# Ninja-towns_modular.net
KiCad netlist of a schematic drawn in EAGLE
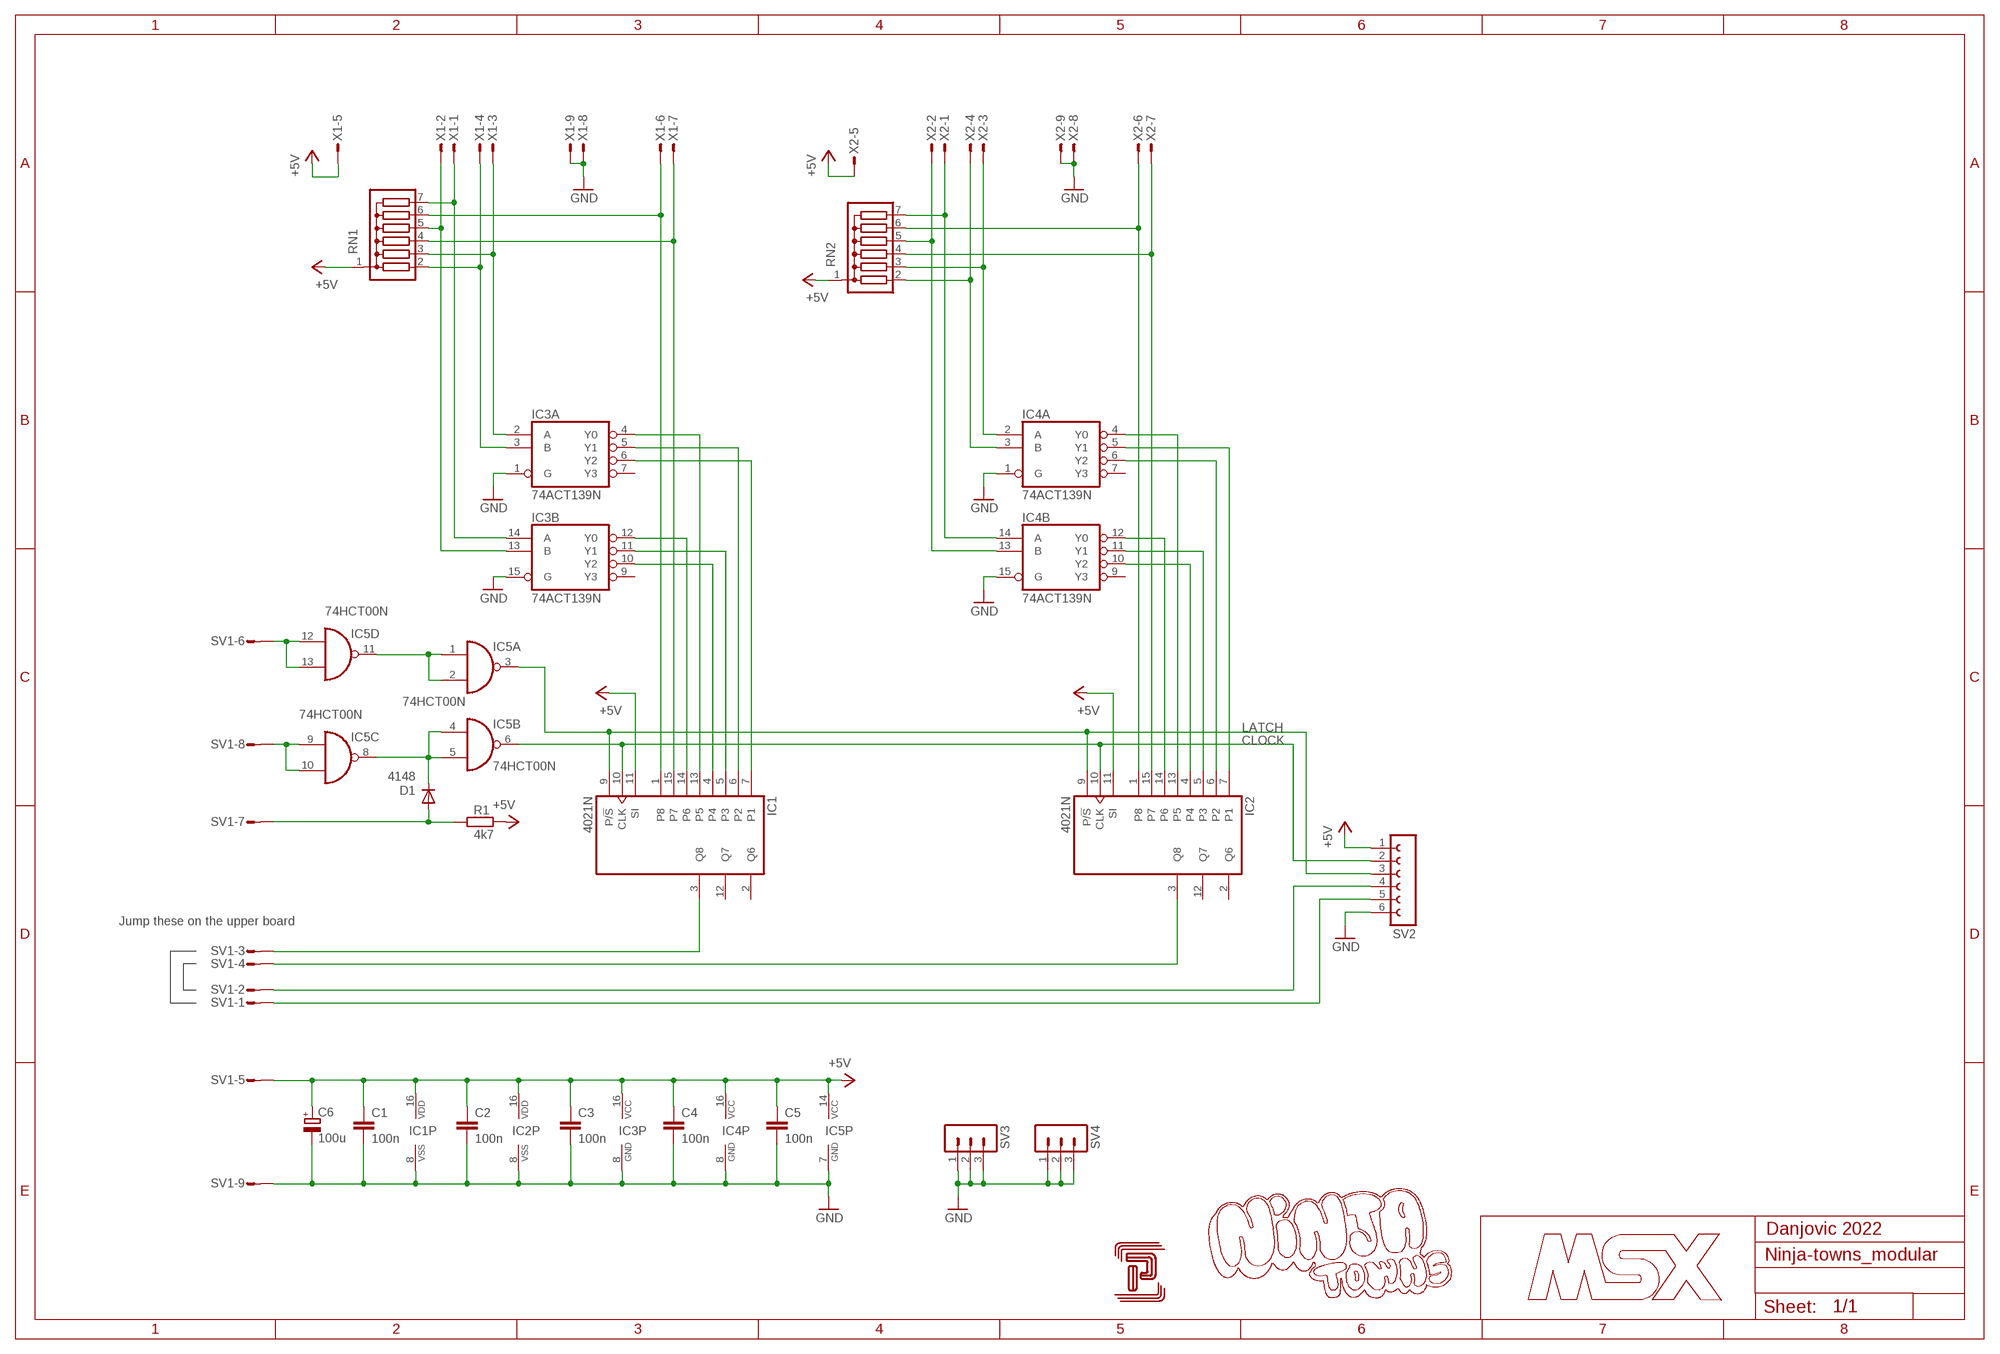
[diagram p0: schematic, sheet 1]

(export (version "E")
  (design (tool "Eeschema 10.0.6"))
  (components
    (comp (ref "C1")
      (value "100n")
      (footprint "eagle-import:C050-024X044")
      (libsource (lib "eagle-import") (part "C-EU050-024X044"))
    )
    (comp (ref "C2")
      (value "100n")
      (footprint "eagle-import:C050-024X044")
      (libsource (lib "eagle-import") (part "C-EU050-024X044"))
    )
    (comp (ref "C3")
      (value "100n")
      (footprint "eagle-import:C050-024X044")
      (libsource (lib "eagle-import") (part "C-EU050-024X044"))
    )
    (comp (ref "C4")
      (value "100n")
      (footprint "eagle-import:C050-024X044")
      (libsource (lib "eagle-import") (part "C-EU050-024X044"))
    )
    (comp (ref "C5")
      (value "100n")
      (footprint "eagle-import:C050-024X044")
      (libsource (lib "eagle-import") (part "C-EU050-024X044"))
    )
    (comp (ref "C6")
      (value "100u")
      (footprint "eagle-import:E2,5-6")
      (libsource (lib "eagle-import") (part "CPOL-EUE2.5-6"))
    )
    (comp (ref "D1")
      (value "4148")
      (footprint "eagle-import:D-5")
      (libsource (lib "eagle-import") (part "DIODE-D-5"))
    )
    (comp (ref "IC1")
      (value "4021N")
      (footprint "eagle-import:DIL16")
      (libsource (lib "eagle-import") (part "4021N"))
    )
    (comp (ref "IC2")
      (value "4021N")
      (footprint "eagle-import:DIL16")
      (libsource (lib "eagle-import") (part "4021N"))
    )
    (comp (ref "IC3")
      (value "74ACT139N")
      (footprint "eagle-import:DIL16")
      (libsource (lib "eagle-import") (part "74139NACT"))
    )
    (comp (ref "IC4")
      (value "74ACT139N")
      (footprint "eagle-import:DIL16")
      (libsource (lib "eagle-import") (part "74139NACT"))
    )
    (comp (ref "IC5")
      (value "74HCT00N")
      (footprint "eagle-import:DIL14")
      (libsource (lib "eagle-import") (part "7400NHCT"))
    )
    (comp (ref "R1")
      (value "4k7")
      (footprint "eagle-import:0204_7L")
      (libsource (lib "eagle-import") (part "R-EU_0204/7L"))
    )
    (comp (ref "RN1")
      (value "G06R")
      (footprint "eagle-import:SIL7")
      (libsource (lib "eagle-import") (part "G06R"))
    )
    (comp (ref "RN2")
      (value "G06R")
      (footprint "eagle-import:SIL7")
      (libsource (lib "eagle-import") (part "G06R"))
    )
    (comp (ref "SV1")
      (value "S09P")
      (footprint "eagle-import:S09P")
      (libsource (lib "eagle-import") (part "S09P"))
    )
    (comp (ref "SV2")
      (value "FE06-1")
      (footprint "eagle-import:FE06")
      (libsource (lib "eagle-import") (part "FE06-1"))
    )
    (comp (ref "SV3")
      (value "MA03-1")
      (footprint "eagle-import:MA03-1")
      (libsource (lib "eagle-import") (part "MA03-1"))
    )
    (comp (ref "SV4")
      (value "MA03-1")
      (footprint "eagle-import:MA03-1")
      (libsource (lib "eagle-import") (part "MA03-1"))
    )
    (comp (ref "U$1")
      (value "PB-203_TOP")
      (footprint "eagle-import:PB203-TOP")
      (libsource (lib "eagle-import") (part "PB-203_TOP"))
    )
    (comp (ref "X1")
      (value "M09-182S")
      (footprint "eagle-import:182-009-MALE")
      (libsource (lib "eagle-import") (part "M09?S-182"))
    )
    (comp (ref "X2")
      (value "M09-182S")
      (footprint "eagle-import:182-009-MALE")
      (libsource (lib "eagle-import") (part "M09?S-182"))
    )
  )
  (nets
    (net (code "1") (name "+5V") (class "Default")
      (node (ref "C1") (pin "1") (pinfunction "1_1") (pintype "passive"))
      (node (ref "C2") (pin "1") (pinfunction "1_1") (pintype "passive"))
      (node (ref "C3") (pin "1") (pinfunction "1_1") (pintype "passive"))
      (node (ref "C4") (pin "1") (pinfunction "1_1") (pintype "passive"))
      (node (ref "C5") (pin "1") (pinfunction "1_1") (pintype "passive"))
      (node (ref "C6") (pin "+") (pinfunction "+_+") (pintype "passive"))
      (node (ref "IC1") (pin "11") (pinfunction "SI_11") (pintype "input"))
      (node (ref "IC1") (pin "16") (pinfunction "VDD_16") (pintype "power_in"))
      (node (ref "IC2") (pin "11") (pinfunction "SI_11") (pintype "input"))
      (node (ref "IC2") (pin "16") (pinfunction "VDD_16") (pintype "power_in"))
      (node (ref "IC3") (pin "16") (pinfunction "VCC_16") (pintype "power_in"))
      (node (ref "IC4") (pin "16") (pinfunction "VCC_16") (pintype "power_in"))
      (node (ref "IC5") (pin "14") (pinfunction "VCC_14") (pintype "power_in"))
      (node (ref "R1") (pin "1") (pinfunction "1_1") (pintype "passive"))
      (node (ref "RN1") (pin "1") (pinfunction "1_1") (pintype "passive"))
      (node (ref "RN2") (pin "1") (pinfunction "1_1") (pintype "passive"))
      (node (ref "SV1") (pin "5") (pinfunction "S_5") (pintype "passive"))
      (node (ref "SV2") (pin "1") (pinfunction "1_1") (pintype "passive"))
      (node (ref "X1") (pin "5") (pinfunction "M_5") (pintype "passive"))
      (node (ref "X2") (pin "5") (pinfunction "M_5") (pintype "passive"))
    )
    (net (code "2") (name "/CLOCK") (class "Default")
      (node (ref "IC1") (pin "10") (pinfunction "CLK_10") (pintype "input"))
      (node (ref "IC2") (pin "10") (pinfunction "CLK_10") (pintype "input"))
      (node (ref "IC5") (pin "6") (pinfunction "O_6") (pintype "output"))
      (node (ref "SV2") (pin "2") (pinfunction "2_2") (pintype "passive"))
    )
    (net (code "3") (name "/LATCH") (class "Default")
      (node (ref "IC1") (pin "9") (pinfunction "P/~{S}_9") (pintype "input"))
      (node (ref "IC2") (pin "9") (pinfunction "P/~{S}_9") (pintype "input"))
      (node (ref "IC5") (pin "3") (pinfunction "O_3") (pintype "output"))
      (node (ref "SV2") (pin "3") (pinfunction "3_3") (pintype "passive"))
    )
    (net (code "4") (name "GND") (class "Default")
      (node (ref "C1") (pin "2") (pinfunction "2_2") (pintype "passive"))
      (node (ref "C2") (pin "2") (pinfunction "2_2") (pintype "passive"))
      (node (ref "C3") (pin "2") (pinfunction "2_2") (pintype "passive"))
      (node (ref "C4") (pin "2") (pinfunction "2_2") (pintype "passive"))
      (node (ref "C5") (pin "2") (pinfunction "2_2") (pintype "passive"))
      (node (ref "C6") (pin "-") (pinfunction "-_-") (pintype "passive"))
      (node (ref "IC1") (pin "8") (pinfunction "VSS_8") (pintype "power_in"))
      (node (ref "IC2") (pin "8") (pinfunction "VSS_8") (pintype "power_in"))
      (node (ref "IC3") (pin "1") (pinfunction "G_1") (pintype "input"))
      (node (ref "IC3") (pin "15") (pinfunction "G_15") (pintype "input"))
      (node (ref "IC3") (pin "8") (pinfunction "GND_8") (pintype "power_in"))
      (node (ref "IC4") (pin "1") (pinfunction "G_1") (pintype "input"))
      (node (ref "IC4") (pin "15") (pinfunction "G_15") (pintype "input"))
      (node (ref "IC4") (pin "8") (pinfunction "GND_8") (pintype "power_in"))
      (node (ref "IC5") (pin "7") (pinfunction "GND_7") (pintype "power_in"))
      (node (ref "SV1") (pin "9") (pinfunction "S_9") (pintype "passive"))
      (node (ref "SV2") (pin "6") (pinfunction "6_6") (pintype "passive"))
      (node (ref "SV3") (pin "1") (pinfunction "1_1") (pintype "passive"))
      (node (ref "SV3") (pin "2") (pinfunction "2_2") (pintype "passive"))
      (node (ref "SV3") (pin "3") (pinfunction "3_3") (pintype "passive"))
      (node (ref "SV4") (pin "1") (pinfunction "1_1") (pintype "passive"))
      (node (ref "SV4") (pin "2") (pinfunction "2_2") (pintype "passive"))
      (node (ref "SV4") (pin "3") (pinfunction "3_3") (pintype "passive"))
      (node (ref "X1") (pin "8") (pinfunction "M_8") (pintype "passive"))
      (node (ref "X1") (pin "9") (pinfunction "M_9") (pintype "passive"))
      (node (ref "X2") (pin "8") (pinfunction "M_8") (pintype "passive"))
      (node (ref "X2") (pin "9") (pinfunction "M_9") (pintype "passive"))
    )
    (net (code "5") (name "Net-(IC1A-P1)") (class "Default")
      (node (ref "IC1") (pin "7") (pinfunction "P1_7") (pintype "input"))
      (node (ref "IC3") (pin "6") (pinfunction "Y2_6") (pintype "output"))
    )
    (net (code "6") (name "Net-(IC1A-P2)") (class "Default")
      (node (ref "IC1") (pin "6") (pinfunction "P2_6") (pintype "input"))
      (node (ref "IC3") (pin "5") (pinfunction "Y1_5") (pintype "output"))
    )
    (net (code "7") (name "Net-(IC1A-P3)") (class "Default")
      (node (ref "IC1") (pin "5") (pinfunction "P3_5") (pintype "input"))
      (node (ref "IC3") (pin "11") (pinfunction "Y1_11") (pintype "output"))
    )
    (net (code "8") (name "Net-(IC1A-P4)") (class "Default")
      (node (ref "IC1") (pin "4") (pinfunction "P4_4") (pintype "input"))
      (node (ref "IC3") (pin "10") (pinfunction "Y2_10") (pintype "output"))
    )
    (net (code "9") (name "Net-(IC1A-P5)") (class "Default")
      (node (ref "IC1") (pin "13") (pinfunction "P5_13") (pintype "input"))
      (node (ref "IC3") (pin "4") (pinfunction "Y0_4") (pintype "output"))
    )
    (net (code "10") (name "Net-(IC1A-P6)") (class "Default")
      (node (ref "IC1") (pin "14") (pinfunction "P6_14") (pintype "input"))
      (node (ref "IC3") (pin "12") (pinfunction "Y0_12") (pintype "output"))
    )
    (net (code "11") (name "Net-(IC1A-P7)") (class "Default")
      (node (ref "IC1") (pin "15") (pinfunction "P7_15") (pintype "input"))
      (node (ref "RN1") (pin "4") (pinfunction "4_4") (pintype "passive"))
      (node (ref "X1") (pin "7") (pinfunction "M_7") (pintype "passive"))
    )
    (net (code "12") (name "Net-(IC1A-P8)") (class "Default")
      (node (ref "IC1") (pin "1") (pinfunction "P8_1") (pintype "input"))
      (node (ref "RN1") (pin "6") (pinfunction "6_6") (pintype "passive"))
      (node (ref "X1") (pin "6") (pinfunction "M_6") (pintype "passive"))
    )
    (net (code "13") (name "Net-(IC1A-Q8)") (class "Default")
      (node (ref "IC1") (pin "3") (pinfunction "Q8_3") (pintype "output"))
      (node (ref "SV1") (pin "3") (pinfunction "S_3") (pintype "passive"))
    )
    (net (code "14") (name "Net-(IC2A-P1)") (class "Default")
      (node (ref "IC2") (pin "7") (pinfunction "P1_7") (pintype "input"))
      (node (ref "IC4") (pin "5") (pinfunction "Y1_5") (pintype "output"))
    )
    (net (code "15") (name "Net-(IC2A-P2)") (class "Default")
      (node (ref "IC2") (pin "6") (pinfunction "P2_6") (pintype "input"))
      (node (ref "IC4") (pin "6") (pinfunction "Y2_6") (pintype "output"))
    )
    (net (code "16") (name "Net-(IC2A-P3)") (class "Default")
      (node (ref "IC2") (pin "5") (pinfunction "P3_5") (pintype "input"))
      (node (ref "IC4") (pin "11") (pinfunction "Y1_11") (pintype "output"))
    )
    (net (code "17") (name "Net-(IC2A-P4)") (class "Default")
      (node (ref "IC2") (pin "4") (pinfunction "P4_4") (pintype "input"))
      (node (ref "IC4") (pin "10") (pinfunction "Y2_10") (pintype "output"))
    )
    (net (code "18") (name "Net-(IC2A-P5)") (class "Default")
      (node (ref "IC2") (pin "13") (pinfunction "P5_13") (pintype "input"))
      (node (ref "IC4") (pin "4") (pinfunction "Y0_4") (pintype "output"))
    )
    (net (code "19") (name "Net-(IC2A-P6)") (class "Default")
      (node (ref "IC2") (pin "14") (pinfunction "P6_14") (pintype "input"))
      (node (ref "IC4") (pin "12") (pinfunction "Y0_12") (pintype "output"))
    )
    (net (code "20") (name "Net-(IC2A-P7)") (class "Default")
      (node (ref "IC2") (pin "15") (pinfunction "P7_15") (pintype "input"))
      (node (ref "RN2") (pin "4") (pinfunction "4_4") (pintype "passive"))
      (node (ref "X2") (pin "7") (pinfunction "M_7") (pintype "passive"))
    )
    (net (code "21") (name "Net-(IC2A-P8)") (class "Default")
      (node (ref "IC2") (pin "1") (pinfunction "P8_1") (pintype "input"))
      (node (ref "RN2") (pin "6") (pinfunction "6_6") (pintype "passive"))
      (node (ref "X2") (pin "6") (pinfunction "M_6") (pintype "passive"))
    )
    (net (code "22") (name "Net-(IC2A-Q8)") (class "Default")
      (node (ref "IC2") (pin "3") (pinfunction "Q8_3") (pintype "output"))
      (node (ref "SV1") (pin "4") (pinfunction "S_4") (pintype "passive"))
    )
    (net (code "23") (name "Net-(IC3A-A)") (class "Default")
      (node (ref "IC3") (pin "2") (pinfunction "A_2") (pintype "input"))
      (node (ref "RN1") (pin "3") (pinfunction "3_3") (pintype "passive"))
      (node (ref "X1") (pin "3") (pinfunction "M_3") (pintype "passive"))
    )
    (net (code "24") (name "Net-(IC3A-B)") (class "Default")
      (node (ref "IC3") (pin "3") (pinfunction "B_3") (pintype "input"))
      (node (ref "RN1") (pin "2") (pinfunction "2_2") (pintype "passive"))
      (node (ref "X1") (pin "4") (pinfunction "M_4") (pintype "passive"))
    )
    (net (code "25") (name "Net-(IC3B-A)") (class "Default")
      (node (ref "IC3") (pin "14") (pinfunction "A_14") (pintype "input"))
      (node (ref "RN1") (pin "7") (pinfunction "7_7") (pintype "passive"))
      (node (ref "X1") (pin "1") (pinfunction "M_1") (pintype "passive"))
    )
    (net (code "26") (name "Net-(IC3B-B)") (class "Default")
      (node (ref "IC3") (pin "13") (pinfunction "B_13") (pintype "input"))
      (node (ref "RN1") (pin "5") (pinfunction "5_5") (pintype "passive"))
      (node (ref "X1") (pin "2") (pinfunction "M_2") (pintype "passive"))
    )
    (net (code "27") (name "Net-(IC4A-A)") (class "Default")
      (node (ref "IC4") (pin "2") (pinfunction "A_2") (pintype "input"))
      (node (ref "RN2") (pin "3") (pinfunction "3_3") (pintype "passive"))
      (node (ref "X2") (pin "3") (pinfunction "M_3") (pintype "passive"))
    )
    (net (code "28") (name "Net-(IC4A-B)") (class "Default")
      (node (ref "IC4") (pin "3") (pinfunction "B_3") (pintype "input"))
      (node (ref "RN2") (pin "2") (pinfunction "2_2") (pintype "passive"))
      (node (ref "X2") (pin "4") (pinfunction "M_4") (pintype "passive"))
    )
    (net (code "29") (name "Net-(IC4B-A)") (class "Default")
      (node (ref "IC4") (pin "14") (pinfunction "A_14") (pintype "input"))
      (node (ref "RN2") (pin "7") (pinfunction "7_7") (pintype "passive"))
      (node (ref "X2") (pin "1") (pinfunction "M_1") (pintype "passive"))
    )
    (net (code "30") (name "Net-(IC4B-B)") (class "Default")
      (node (ref "IC4") (pin "13") (pinfunction "B_13") (pintype "input"))
      (node (ref "RN2") (pin "5") (pinfunction "5_5") (pintype "passive"))
      (node (ref "X2") (pin "2") (pinfunction "M_2") (pintype "passive"))
    )
    (net (code "31") (name "Net-(IC5A-I0)") (class "Default")
      (node (ref "IC5") (pin "1") (pinfunction "I0_1") (pintype "input"))
      (node (ref "IC5") (pin "11") (pinfunction "O_11") (pintype "output"))
      (node (ref "IC5") (pin "2") (pinfunction "I1_2") (pintype "input"))
    )
    (net (code "32") (name "Net-(IC5B-I0)") (class "Default")
      (node (ref "D1") (pin "C") (pinfunction "C_C") (pintype "passive"))
      (node (ref "IC5") (pin "4") (pinfunction "I0_4") (pintype "input"))
      (node (ref "IC5") (pin "5") (pinfunction "I1_5") (pintype "input"))
      (node (ref "IC5") (pin "8") (pinfunction "O_8") (pintype "output"))
    )
    (net (code "33") (name "Net-(IC5C-I0)") (class "Default")
      (node (ref "IC5") (pin "10") (pinfunction "I1_10") (pintype "input"))
      (node (ref "IC5") (pin "9") (pinfunction "I0_9") (pintype "input"))
      (node (ref "SV1") (pin "8") (pinfunction "S_8") (pintype "passive"))
    )
    (net (code "34") (name "Net-(IC5D-I0)") (class "Default")
      (node (ref "IC5") (pin "12") (pinfunction "I0_12") (pintype "input"))
      (node (ref "IC5") (pin "13") (pinfunction "I1_13") (pintype "input"))
      (node (ref "SV1") (pin "6") (pinfunction "S_6") (pintype "passive"))
    )
    (net (code "35") (name "Net-(SV1A-S)") (class "Default")
      (node (ref "SV1") (pin "1") (pinfunction "S_1") (pintype "passive"))
      (node (ref "SV2") (pin "5") (pinfunction "5_5") (pintype "passive"))
    )
    (net (code "36") (name "Net-(SV1B-S)") (class "Default")
      (node (ref "SV1") (pin "2") (pinfunction "S_2") (pintype "passive"))
      (node (ref "SV2") (pin "4") (pinfunction "4_4") (pintype "passive"))
    )
    (net (code "37") (name "Net-(SV1G-S)") (class "Default")
      (node (ref "D1") (pin "A") (pinfunction "A_A") (pintype "passive"))
      (node (ref "R1") (pin "2") (pinfunction "2_2") (pintype "passive"))
      (node (ref "SV1") (pin "7") (pinfunction "S_7") (pintype "passive"))
    )
    (net (code "38") (name "unconnected-(IC1A-Q6-Pad2)") (class "Default")
      (node (ref "IC1") (pin "2") (pinfunction "Q6_2") (pintype "output"))
    )
    (net (code "39") (name "unconnected-(IC1A-Q7-Pad12)") (class "Default")
      (node (ref "IC1") (pin "12") (pinfunction "Q7_12") (pintype "output"))
    )
    (net (code "40") (name "unconnected-(IC2A-Q6-Pad2)") (class "Default")
      (node (ref "IC2") (pin "2") (pinfunction "Q6_2") (pintype "output"))
    )
    (net (code "41") (name "unconnected-(IC2A-Q7-Pad12)") (class "Default")
      (node (ref "IC2") (pin "12") (pinfunction "Q7_12") (pintype "output"))
    )
    (net (code "42") (name "unconnected-(IC3A-Y3-Pad7)") (class "Default")
      (node (ref "IC3") (pin "7") (pinfunction "Y3_7") (pintype "output"))
    )
    (net (code "43") (name "unconnected-(IC3B-Y3-Pad9)") (class "Default")
      (node (ref "IC3") (pin "9") (pinfunction "Y3_9") (pintype "output"))
    )
    (net (code "44") (name "unconnected-(IC4A-Y3-Pad7)") (class "Default")
      (node (ref "IC4") (pin "7") (pinfunction "Y3_7") (pintype "output"))
    )
    (net (code "45") (name "unconnected-(IC4B-Y3-Pad9)") (class "Default")
      (node (ref "IC4") (pin "9") (pinfunction "Y3_9") (pintype "output"))
    )
  )
)
